# datalogger1.net
KiCad netlist of a schematic drawn in EAGLE
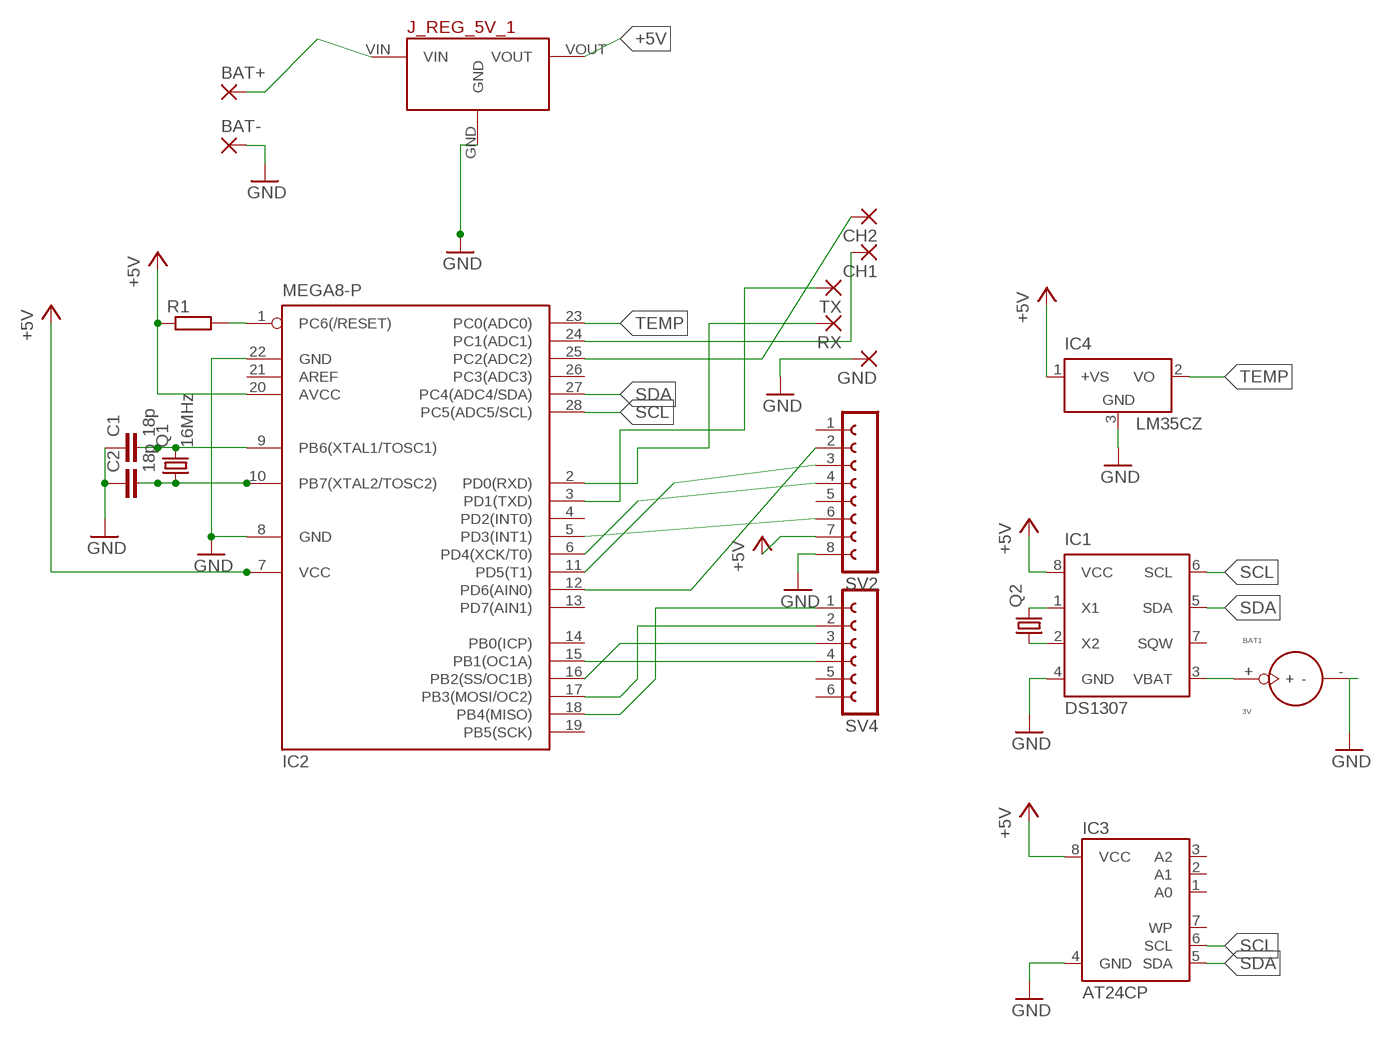
[diagram p0: schematic, sheet 1]

(export (version "E")
  (design (tool "Eeschema 10.0.6"))
  (components
    (comp (ref "BAT+")
      (value "2,54/1,0")
      (footprint "eagle-import:2,54_1,0")
      (libsource (lib "eagle-import") (part "2,54/1,0"))
    )
    (comp (ref "BAT-")
      (value "2,54/1,0")
      (footprint "eagle-import:2,54_1,0")
      (libsource (lib "eagle-import") (part "2,54/1,0"))
    )
    (comp (ref "BAT1")
      (value "3V")
      (footprint "eagle-import:BATTERY_1236_C")
      (libsource (lib "eagle-import") (part "BATTERY_1236_C"))
    )
    (comp (ref "C1")
      (value "18p")
      (footprint "eagle-import:C050-024X044")
      (libsource (lib "eagle-import") (part "C-EU050-024X044"))
    )
    (comp (ref "C2")
      (value "18p")
      (footprint "eagle-import:C050-024X044")
      (libsource (lib "eagle-import") (part "C-EU050-024X044"))
    )
    (comp (ref "CH1")
      (value "1,6/0,8")
      (footprint "eagle-import:1,6_0,8")
      (libsource (lib "eagle-import") (part "1,6/0,8"))
    )
    (comp (ref "CH2")
      (value "1,6/0,8")
      (footprint "eagle-import:1,6_0,8")
      (libsource (lib "eagle-import") (part "1,6/0,8"))
    )
    (comp (ref "GND")
      (value "1,6/0,8")
      (footprint "eagle-import:1,6_0,8")
      (libsource (lib "eagle-import") (part "1,6/0,8"))
    )
    (comp (ref "IC1")
      (value "DS1307")
      (footprint "eagle-import:DIL08")
      (libsource (lib "eagle-import") (part "DS1307"))
    )
    (comp (ref "IC2")
      (value "MEGA8-P")
      (footprint "eagle-import:DIL28-3")
      (libsource (lib "eagle-import") (part "MEGA8-P"))
    )
    (comp (ref "IC3")
      (value "AT24CP")
      (footprint "eagle-import:DIL08")
      (fields (field (name "MPN") "AT24C1024BW-SH-B"))
      (libsource (lib "eagle-import") (part "AT24CP"))
    )
    (comp (ref "IC4")
      (value "LM35CZ")
      (footprint "eagle-import:TO92")
      (libsource (lib "eagle-import") (part "LM35CZ"))
    )
    (comp (ref "J_REG_5V_1")
      (value "5V_VOLTAGE_REGULATOR")
      (footprint "eagle-import:5V_VOLTAGE_REGULATOR")
      (libsource (lib "eagle-import") (part "5V_VOLTAGE_REGULATOR"))
    )
    (comp (ref "Q1")
      (value "16MHz")
      (footprint "eagle-import:HC49_S")
      (libsource (lib "eagle-import") (part "CRYSTALHC49S"))
    )
    (comp (ref "Q2")
      (value "CRYSTALTC38H")
      (footprint "eagle-import:TC38H")
      (libsource (lib "eagle-import") (part "CRYSTALTC38H"))
    )
    (comp (ref "R1")
      (value "R-EU_0204/7")
      (footprint "eagle-import:0204_7")
      (libsource (lib "eagle-import") (part "R-EU_0204/7"))
    )
    (comp (ref "RX")
      (value "1,6/0,8")
      (footprint "eagle-import:1,6_0,8")
      (libsource (lib "eagle-import") (part "1,6/0,8"))
    )
    (comp (ref "SV2")
      (value "FE08-1")
      (footprint "eagle-import:FE08")
      (libsource (lib "eagle-import") (part "FE08-1"))
    )
    (comp (ref "SV4")
      (value "FE06-1")
      (footprint "eagle-import:FE06")
      (libsource (lib "eagle-import") (part "FE06-1"))
    )
    (comp (ref "TX")
      (value "1,6/0,8")
      (footprint "eagle-import:1,6_0,8")
      (libsource (lib "eagle-import") (part "1,6/0,8"))
    )
  )
  (nets
    (net (code "1") (name "+5V") (class "Default")
      (node (ref "IC1") (pin "8") (pinfunction "VCC_8") (pintype "power_in"))
      (node (ref "IC2") (pin "20") (pinfunction "AVCC_20") (pintype "power_in"))
      (node (ref "IC2") (pin "7") (pinfunction "VCC_7") (pintype "power_in"))
      (node (ref "IC3") (pin "8") (pinfunction "VCC_8") (pintype "power_in"))
      (node (ref "IC4") (pin "1") (pinfunction "+VS_1") (pintype "input"))
      (node (ref "J_REG_5V_1") (pin "VOUT") (pinfunction "VOUT_VOUT") (pintype "bidirectional"))
      (node (ref "R1") (pin "1") (pinfunction "1_1") (pintype "passive"))
      (node (ref "SV2") (pin "7") (pinfunction "7_7") (pintype "passive"))
    )
    (net (code "2") (name "GND") (class "Default")
      (node (ref "BAT-") (pin "1") (pinfunction "P_1") (pintype "passive"))
      (node (ref "BAT1") (pin "-") (pinfunction "-_-") (pintype "bidirectional"))
      (node (ref "C1") (pin "1") (pinfunction "1_1") (pintype "passive"))
      (node (ref "C2") (pin "1") (pinfunction "1_1") (pintype "passive"))
      (node (ref "GND") (pin "1") (pinfunction "P_1") (pintype "passive"))
      (node (ref "IC1") (pin "4") (pinfunction "GND_4") (pintype "power_in"))
      (node (ref "IC2") (pin "22") (pinfunction "GND_22") (pintype "power_in"))
      (node (ref "IC2") (pin "8") (pinfunction "GND_8") (pintype "power_in"))
      (node (ref "IC3") (pin "4") (pinfunction "GND_4") (pintype "power_in"))
      (node (ref "IC4") (pin "3") (pinfunction "GND_3") (pintype "power_in"))
      (node (ref "J_REG_5V_1") (pin "GND") (pinfunction "GND_GND") (pintype "bidirectional"))
      (node (ref "SV2") (pin "8") (pinfunction "8_8") (pintype "passive"))
    )
    (net (code "3") (name "Net-(BAT+-P)") (class "Default")
      (node (ref "BAT+") (pin "1") (pinfunction "P_1") (pintype "passive"))
      (node (ref "J_REG_5V_1") (pin "VIN") (pinfunction "VIN_VIN") (pintype "bidirectional"))
    )
    (net (code "4") (name "Net-(CH1-P)") (class "Default")
      (node (ref "CH1") (pin "1") (pinfunction "P_1") (pintype "passive"))
      (node (ref "IC2") (pin "24") (pinfunction "PC1(ADC1)_24") (pintype "bidirectional"))
    )
    (net (code "5") (name "Net-(CH2-P)") (class "Default")
      (node (ref "CH2") (pin "1") (pinfunction "P_1") (pintype "passive"))
      (node (ref "IC2") (pin "25") (pinfunction "PC2(ADC2)_25") (pintype "bidirectional"))
    )
    (net (code "6") (name "Net-(IC1-VBAT)") (class "Default")
      (node (ref "BAT1") (pin "+") (pinfunction "+_+") (pintype "bidirectional"))
      (node (ref "IC1") (pin "3") (pinfunction "VBAT_3") (pintype "passive"))
    )
    (net (code "7") (name "Net-(IC1-X1)") (class "Default")
      (node (ref "IC1") (pin "1") (pinfunction "X1_1") (pintype "input"))
      (node (ref "Q2") (pin "2") (pinfunction "2_2") (pintype "passive"))
    )
    (net (code "8") (name "Net-(IC1-X2)") (class "Default")
      (node (ref "IC1") (pin "2") (pinfunction "X2_2") (pintype "output"))
      (node (ref "Q2") (pin "1") (pinfunction "1_1") (pintype "passive"))
    )
    (net (code "9") (name "Net-(IC2-PB1(OC1A))") (class "Default")
      (node (ref "IC2") (pin "15") (pinfunction "PB1(OC1A)_15") (pintype "bidirectional"))
      (node (ref "SV4") (pin "4") (pinfunction "4_4") (pintype "passive"))
    )
    (net (code "10") (name "Net-(IC2-PB2(SS{slash}OC1B))") (class "Default")
      (node (ref "IC2") (pin "16") (pinfunction "PB2(SS/OC1B)_16") (pintype "bidirectional"))
      (node (ref "SV4") (pin "3") (pinfunction "3_3") (pintype "passive"))
    )
    (net (code "11") (name "Net-(IC2-PB3(MOSI{slash}OC2))") (class "Default")
      (node (ref "IC2") (pin "17") (pinfunction "PB3(MOSI/OC2)_17") (pintype "bidirectional"))
      (node (ref "SV4") (pin "2") (pinfunction "2_2") (pintype "passive"))
    )
    (net (code "12") (name "Net-(IC2-PB4(MISO))") (class "Default")
      (node (ref "IC2") (pin "18") (pinfunction "PB4(MISO)_18") (pintype "bidirectional"))
      (node (ref "SV4") (pin "1") (pinfunction "1_1") (pintype "passive"))
    )
    (net (code "13") (name "Net-(IC2-PB6(XTAL1{slash}TOSC1))") (class "Default")
      (node (ref "C1") (pin "2") (pinfunction "2_2") (pintype "passive"))
      (node (ref "IC2") (pin "9") (pinfunction "PB6(XTAL1/TOSC1)_9") (pintype "bidirectional"))
      (node (ref "Q1") (pin "2") (pinfunction "2_2") (pintype "passive"))
    )
    (net (code "14") (name "Net-(IC2-PB7(XTAL2{slash}TOSC2))") (class "Default")
      (node (ref "C2") (pin "2") (pinfunction "2_2") (pintype "passive"))
      (node (ref "IC2") (pin "10") (pinfunction "PB7(XTAL2/TOSC2)_10") (pintype "bidirectional"))
      (node (ref "Q1") (pin "1") (pinfunction "1_1") (pintype "passive"))
    )
    (net (code "15") (name "Net-(IC2-PC6({slash}RESET))") (class "Default")
      (node (ref "IC2") (pin "1") (pinfunction "PC6(/RESET)_1") (pintype "bidirectional"))
      (node (ref "R1") (pin "2") (pinfunction "2_2") (pintype "passive"))
    )
    (net (code "16") (name "Net-(IC2-PD0(RXD))") (class "Default")
      (node (ref "IC2") (pin "2") (pinfunction "PD0(RXD)_2") (pintype "bidirectional"))
      (node (ref "RX") (pin "1") (pinfunction "P_1") (pintype "passive"))
    )
    (net (code "17") (name "Net-(IC2-PD1(TXD))") (class "Default")
      (node (ref "IC2") (pin "3") (pinfunction "PD1(TXD)_3") (pintype "bidirectional"))
      (node (ref "TX") (pin "1") (pinfunction "P_1") (pintype "passive"))
    )
    (net (code "18") (name "Net-(IC2-PD3(INT1))") (class "Default")
      (node (ref "IC2") (pin "5") (pinfunction "PD3(INT1)_5") (pintype "bidirectional"))
      (node (ref "SV2") (pin "6") (pinfunction "6_6") (pintype "passive"))
    )
    (net (code "19") (name "Net-(IC2-PD4(XCK{slash}T0))") (class "Default")
      (node (ref "IC2") (pin "6") (pinfunction "PD4(XCK/T0)_6") (pintype "bidirectional"))
      (node (ref "SV2") (pin "4") (pinfunction "4_4") (pintype "passive"))
    )
    (net (code "20") (name "Net-(IC2-PD5(T1))") (class "Default")
      (node (ref "IC2") (pin "11") (pinfunction "PD5(T1)_11") (pintype "bidirectional"))
      (node (ref "SV2") (pin "3") (pinfunction "3_3") (pintype "passive"))
    )
    (net (code "21") (name "Net-(IC2-PD6(AIN0))") (class "Default")
      (node (ref "IC2") (pin "12") (pinfunction "PD6(AIN0)_12") (pintype "bidirectional"))
      (node (ref "SV2") (pin "2") (pinfunction "2_2") (pintype "passive"))
    )
    (net (code "22") (name "SCL") (class "Default")
      (node (ref "IC1") (pin "6") (pinfunction "SCL_6") (pintype "input"))
      (node (ref "IC2") (pin "28") (pinfunction "PC5(ADC5/SCL)_28") (pintype "bidirectional"))
      (node (ref "IC3") (pin "6") (pinfunction "SCL_6") (pintype "bidirectional"))
    )
    (net (code "23") (name "SDA") (class "Default")
      (node (ref "IC1") (pin "5") (pinfunction "SDA_5") (pintype "bidirectional"))
      (node (ref "IC2") (pin "27") (pinfunction "PC4(ADC4/SDA)_27") (pintype "bidirectional"))
      (node (ref "IC3") (pin "5") (pinfunction "SDA_5") (pintype "bidirectional"))
    )
    (net (code "24") (name "TEMP") (class "Default")
      (node (ref "IC2") (pin "23") (pinfunction "PC0(ADC0)_23") (pintype "bidirectional"))
      (node (ref "IC4") (pin "2") (pinfunction "VO_2") (pintype "input"))
    )
    (net (code "25") (name "unconnected-(IC1-SQW-Pad7)") (class "Default")
      (node (ref "IC1") (pin "7") (pinfunction "SQW_7") (pintype "open_collector"))
    )
    (net (code "26") (name "unconnected-(IC2-AREF-Pad21)") (class "Default")
      (node (ref "IC2") (pin "21") (pinfunction "AREF_21") (pintype "passive"))
    )
    (net (code "27") (name "unconnected-(IC2-PB0(ICP)-Pad14)") (class "Default")
      (node (ref "IC2") (pin "14") (pinfunction "PB0(ICP)_14") (pintype "bidirectional"))
    )
    (net (code "28") (name "unconnected-(IC2-PB5(SCK)-Pad19)") (class "Default")
      (node (ref "IC2") (pin "19") (pinfunction "PB5(SCK)_19") (pintype "bidirectional"))
    )
    (net (code "29") (name "unconnected-(IC2-PC3(ADC3)-Pad26)") (class "Default")
      (node (ref "IC2") (pin "26") (pinfunction "PC3(ADC3)_26") (pintype "bidirectional"))
    )
    (net (code "30") (name "unconnected-(IC2-PD2(INT0)-Pad4)") (class "Default")
      (node (ref "IC2") (pin "4") (pinfunction "PD2(INT0)_4") (pintype "bidirectional"))
    )
    (net (code "31") (name "unconnected-(IC2-PD7(AIN1)-Pad13)") (class "Default")
      (node (ref "IC2") (pin "13") (pinfunction "PD7(AIN1)_13") (pintype "bidirectional"))
    )
    (net (code "32") (name "unconnected-(IC3-A0-Pad1)") (class "Default")
      (node (ref "IC3") (pin "1") (pinfunction "A0_1") (pintype "input"))
    )
    (net (code "33") (name "unconnected-(IC3-A1-Pad2)") (class "Default")
      (node (ref "IC3") (pin "2") (pinfunction "A1_2") (pintype "input"))
    )
    (net (code "34") (name "unconnected-(IC3-A2-Pad3)") (class "Default")
      (node (ref "IC3") (pin "3") (pinfunction "A2_3") (pintype "input"))
    )
    (net (code "35") (name "unconnected-(IC3-WP-Pad7)") (class "Default")
      (node (ref "IC3") (pin "7") (pinfunction "WP_7") (pintype "input"))
    )
    (net (code "36") (name "unconnected-(SV2-Pad1)") (class "Default")
      (node (ref "SV2") (pin "1") (pinfunction "1_1") (pintype "passive"))
    )
    (net (code "37") (name "unconnected-(SV2-Pad5)") (class "Default")
      (node (ref "SV2") (pin "5") (pinfunction "5_5") (pintype "passive"))
    )
    (net (code "38") (name "unconnected-(SV4-Pad5)") (class "Default")
      (node (ref "SV4") (pin "5") (pinfunction "5_5") (pintype "passive"))
    )
    (net (code "39") (name "unconnected-(SV4-Pad6)") (class "Default")
      (node (ref "SV4") (pin "6") (pinfunction "6_6") (pintype "passive"))
    )
  )
)
